# IR_array.net
KiCad netlist of a schematic drawn in Altium Designer
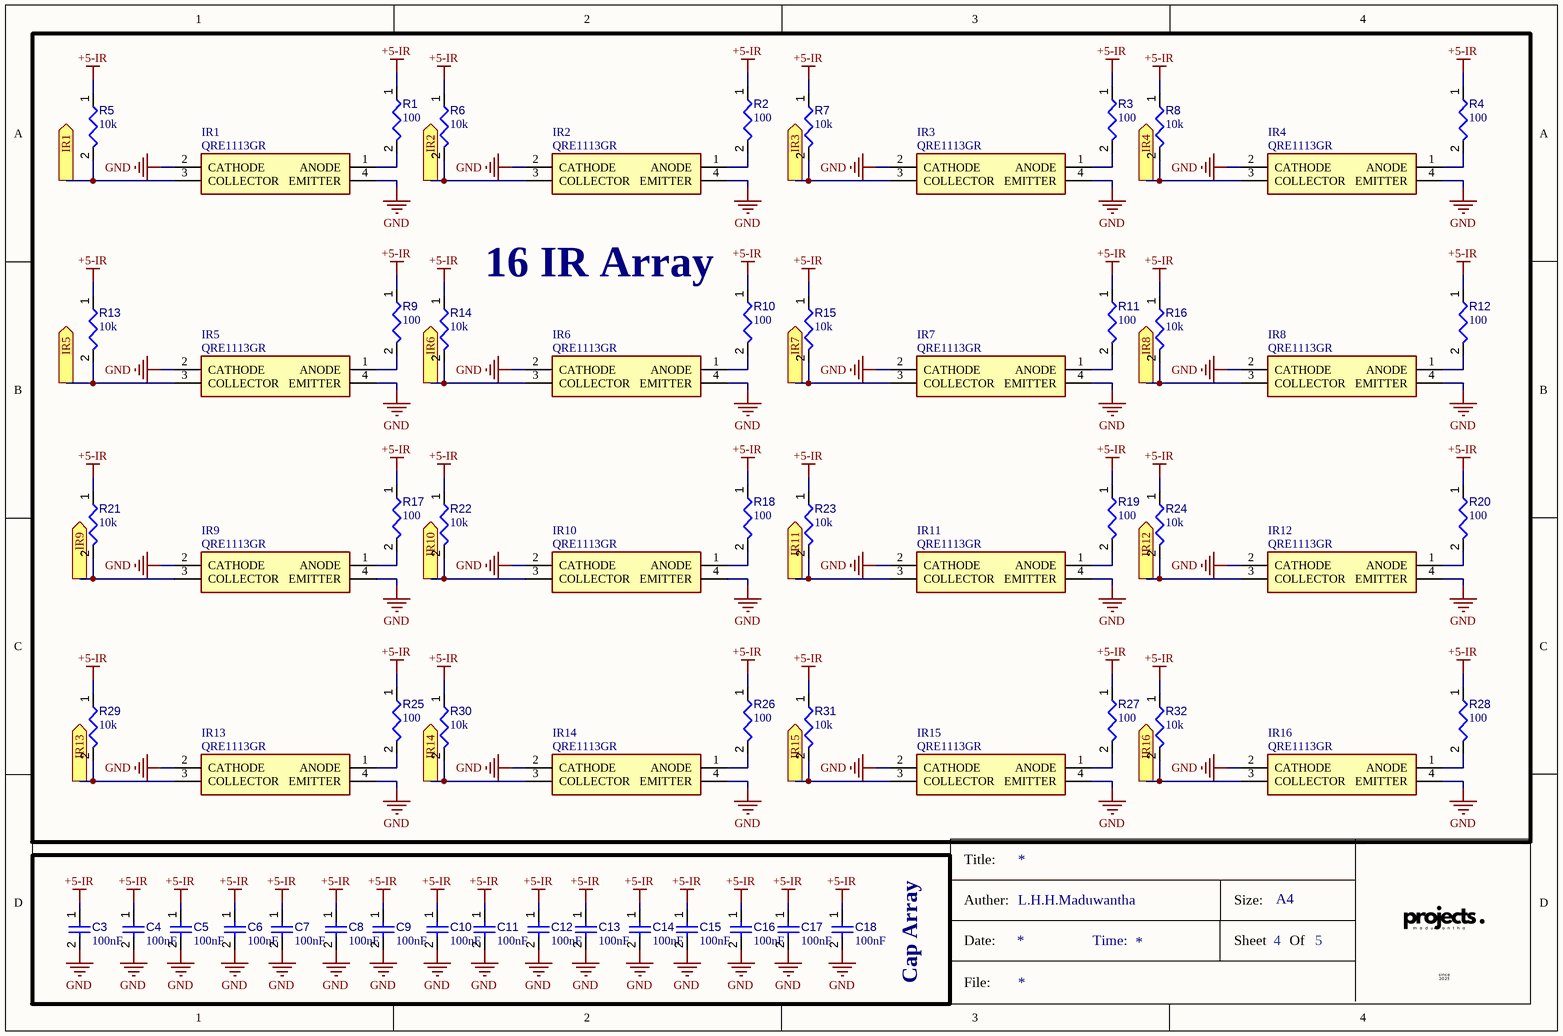
[diagram p0: IR_array.SchDoc]

(export (version "E")
  (design (tool "Eeschema 10.0.6"))
  (components
    (comp (ref "C3")
      (value "100nF")
      (footprint "CAPC2013X95X50LL10T25")
      (description "Chip Capacitor, 100 nF, +/- 10%, 50 V, 0805 (2012 Metric)")
      (fields (field (name "TOLERANCE") "10%") (field (name "Comment") "Capacitor 100 nF +/-10% 50 V 0805"))
      (libsource (lib "EDR Project") (part "CAP-NP-2"))
    )
    (comp (ref "C4")
      (value "100nF")
      (footprint "CAPC2013X95X50LL10T25")
      (description "Chip Capacitor, 100 nF, +/- 10%, 50 V, 0805 (2012 Metric)")
      (fields (field (name "TOLERANCE") "10%") (field (name "Comment") "Capacitor 100 nF +/-10% 50 V 0805"))
      (libsource (lib "EDR Project") (part "CAP-NP-2"))
    )
    (comp (ref "C5")
      (value "100nF")
      (footprint "CAPC2013X95X50LL10T25")
      (description "Chip Capacitor, 100 nF, +/- 10%, 50 V, 0805 (2012 Metric)")
      (fields (field (name "TOLERANCE") "10%") (field (name "Comment") "Capacitor 100 nF +/-10% 50 V 0805"))
      (libsource (lib "EDR Project") (part "CAP-NP-2"))
    )
    (comp (ref "C6")
      (value "100nF")
      (footprint "CAPC2013X95X50LL10T25")
      (description "Chip Capacitor, 100 nF, +/- 10%, 50 V, 0805 (2012 Metric)")
      (fields (field (name "TOLERANCE") "10%") (field (name "Comment") "Capacitor 100 nF +/-10% 50 V 0805"))
      (libsource (lib "EDR Project") (part "CAP-NP-2"))
    )
    (comp (ref "C7")
      (value "100nF")
      (footprint "CAPC2013X95X50LL10T25")
      (description "Chip Capacitor, 100 nF, +/- 10%, 50 V, 0805 (2012 Metric)")
      (fields (field (name "TOLERANCE") "10%") (field (name "Comment") "Capacitor 100 nF +/-10% 50 V 0805"))
      (libsource (lib "EDR Project") (part "CAP-NP-2"))
    )
    (comp (ref "C8")
      (value "100nF")
      (footprint "CAPC2013X95X50LL10T25")
      (description "Chip Capacitor, 100 nF, +/- 10%, 50 V, 0805 (2012 Metric)")
      (fields (field (name "TOLERANCE") "10%") (field (name "Comment") "Capacitor 100 nF +/-10% 50 V 0805"))
      (libsource (lib "EDR Project") (part "CAP-NP-2"))
    )
    (comp (ref "C9")
      (value "100nF")
      (footprint "CAPC2013X95X50LL10T25")
      (description "Chip Capacitor, 100 nF, +/- 10%, 50 V, 0805 (2012 Metric)")
      (fields (field (name "TOLERANCE") "10%") (field (name "Comment") "Capacitor 100 nF +/-10% 50 V 0805"))
      (libsource (lib "EDR Project") (part "CAP-NP-2"))
    )
    (comp (ref "C10")
      (value "100nF")
      (footprint "CAPC2013X95X50LL10T25")
      (description "Chip Capacitor, 100 nF, +/- 10%, 50 V, 0805 (2012 Metric)")
      (fields (field (name "TOLERANCE") "10%") (field (name "Comment") "Capacitor 100 nF +/-10% 50 V 0805"))
      (libsource (lib "EDR Project") (part "CAP-NP-2"))
    )
    (comp (ref "C11")
      (value "100nF")
      (footprint "CAPC2013X95X50LL10T25")
      (description "Chip Capacitor, 100 nF, +/- 10%, 50 V, 0805 (2012 Metric)")
      (fields (field (name "TOLERANCE") "10%") (field (name "Comment") "Capacitor 100 nF +/-10% 50 V 0805"))
      (libsource (lib "EDR Project") (part "CAP-NP-2"))
    )
    (comp (ref "C12")
      (value "100nF")
      (footprint "CAPC2013X95X50LL10T25")
      (description "Chip Capacitor, 100 nF, +/- 10%, 50 V, 0805 (2012 Metric)")
      (fields (field (name "TOLERANCE") "10%") (field (name "Comment") "Capacitor 100 nF +/-10% 50 V 0805"))
      (libsource (lib "EDR Project") (part "CAP-NP-2"))
    )
    (comp (ref "C13")
      (value "100nF")
      (footprint "CAPC2013X95X50LL10T25")
      (description "Chip Capacitor, 100 nF, +/- 10%, 50 V, 0805 (2012 Metric)")
      (fields (field (name "TOLERANCE") "10%") (field (name "Comment") "Capacitor 100 nF +/-10% 50 V 0805"))
      (libsource (lib "EDR Project") (part "CAP-NP-2"))
    )
    (comp (ref "C14")
      (value "100nF")
      (footprint "CAPC2013X95X50LL10T25")
      (description "Chip Capacitor, 100 nF, +/- 10%, 50 V, 0805 (2012 Metric)")
      (fields (field (name "TOLERANCE") "10%") (field (name "Comment") "Capacitor 100 nF +/-10% 50 V 0805"))
      (libsource (lib "EDR Project") (part "CAP-NP-2"))
    )
    (comp (ref "C15")
      (value "100nF")
      (footprint "CAPC2013X95X50LL10T25")
      (description "Chip Capacitor, 100 nF, +/- 10%, 50 V, 0805 (2012 Metric)")
      (fields (field (name "TOLERANCE") "10%") (field (name "Comment") "Capacitor 100 nF +/-10% 50 V 0805"))
      (libsource (lib "EDR Project") (part "CAP-NP-2"))
    )
    (comp (ref "C16")
      (value "100nF")
      (footprint "CAPC2013X95X50LL10T25")
      (description "Chip Capacitor, 100 nF, +/- 10%, 50 V, 0805 (2012 Metric)")
      (fields (field (name "TOLERANCE") "10%") (field (name "Comment") "Capacitor 100 nF +/-10% 50 V 0805"))
      (libsource (lib "EDR Project") (part "CAP-NP-2"))
    )
    (comp (ref "C17")
      (value "100nF")
      (footprint "CAPC2013X95X50LL10T25")
      (description "Chip Capacitor, 100 nF, +/- 10%, 50 V, 0805 (2012 Metric)")
      (fields (field (name "TOLERANCE") "10%") (field (name "Comment") "Capacitor 100 nF +/-10% 50 V 0805"))
      (libsource (lib "EDR Project") (part "CAP-NP-2"))
    )
    (comp (ref "C18")
      (value "100nF")
      (footprint "CAPC2013X95X50LL10T25")
      (description "Chip Capacitor, 100 nF, +/- 10%, 50 V, 0805 (2012 Metric)")
      (fields (field (name "TOLERANCE") "10%") (field (name "Comment") "Capacitor 100 nF +/-10% 50 V 0805"))
      (libsource (lib "EDR Project") (part "CAP-NP-2"))
    )
    (comp (ref "IR1")
      (value "QRE1113GR")
      (footprint "SamacSys:QRE1113GR")
      (description "Undefined or Miscellaneous")
      (fields (field (name "MOUSER PART NUMBER") "512-QRE1113GR"))
      (libsource (lib "*") (part "QRE1113GR"))
    )
    (comp (ref "IR2")
      (value "QRE1113GR")
      (footprint "SamacSys:QRE1113GR")
      (description "Undefined or Miscellaneous")
      (fields (field (name "MOUSER PART NUMBER") "512-QRE1113GR"))
      (libsource (lib "*") (part "QRE1113GR"))
    )
    (comp (ref "IR3")
      (value "QRE1113GR")
      (footprint "SamacSys:QRE1113GR")
      (description "Undefined or Miscellaneous")
      (fields (field (name "MOUSER PART NUMBER") "512-QRE1113GR"))
      (libsource (lib "*") (part "QRE1113GR"))
    )
    (comp (ref "IR4")
      (value "QRE1113GR")
      (footprint "SamacSys:QRE1113GR")
      (description "Undefined or Miscellaneous")
      (fields (field (name "MOUSER PART NUMBER") "512-QRE1113GR"))
      (libsource (lib "*") (part "QRE1113GR"))
    )
    (comp (ref "IR5")
      (value "QRE1113GR")
      (footprint "SamacSys:QRE1113GR")
      (description "Undefined or Miscellaneous")
      (fields (field (name "MOUSER PART NUMBER") "512-QRE1113GR"))
      (libsource (lib "*") (part "QRE1113GR"))
    )
    (comp (ref "IR6")
      (value "QRE1113GR")
      (footprint "SamacSys:QRE1113GR")
      (description "Undefined or Miscellaneous")
      (fields (field (name "MOUSER PART NUMBER") "512-QRE1113GR"))
      (libsource (lib "*") (part "QRE1113GR"))
    )
    (comp (ref "IR7")
      (value "QRE1113GR")
      (footprint "SamacSys:QRE1113GR")
      (description "Undefined or Miscellaneous")
      (fields (field (name "MOUSER PART NUMBER") "512-QRE1113GR"))
      (libsource (lib "*") (part "QRE1113GR"))
    )
    (comp (ref "IR8")
      (value "QRE1113GR")
      (footprint "SamacSys:QRE1113GR")
      (description "Undefined or Miscellaneous")
      (fields (field (name "MOUSER PART NUMBER") "512-QRE1113GR"))
      (libsource (lib "*") (part "QRE1113GR"))
    )
    (comp (ref "IR9")
      (value "QRE1113GR")
      (footprint "SamacSys:QRE1113GR")
      (description "Undefined or Miscellaneous")
      (fields (field (name "MOUSER PART NUMBER") "512-QRE1113GR"))
      (libsource (lib "*") (part "QRE1113GR"))
    )
    (comp (ref "IR10")
      (value "QRE1113GR")
      (footprint "SamacSys:QRE1113GR")
      (description "Undefined or Miscellaneous")
      (fields (field (name "MOUSER PART NUMBER") "512-QRE1113GR"))
      (libsource (lib "*") (part "QRE1113GR"))
    )
    (comp (ref "IR11")
      (value "QRE1113GR")
      (footprint "SamacSys:QRE1113GR")
      (description "Undefined or Miscellaneous")
      (fields (field (name "MOUSER PART NUMBER") "512-QRE1113GR"))
      (libsource (lib "*") (part "QRE1113GR"))
    )
    (comp (ref "IR12")
      (value "QRE1113GR")
      (footprint "SamacSys:QRE1113GR")
      (description "Undefined or Miscellaneous")
      (fields (field (name "MOUSER PART NUMBER") "512-QRE1113GR"))
      (libsource (lib "*") (part "QRE1113GR"))
    )
    (comp (ref "IR13")
      (value "QRE1113GR")
      (footprint "SamacSys:QRE1113GR")
      (description "Undefined or Miscellaneous")
      (fields (field (name "MOUSER PART NUMBER") "512-QRE1113GR"))
      (libsource (lib "*") (part "QRE1113GR"))
    )
    (comp (ref "IR14")
      (value "QRE1113GR")
      (footprint "SamacSys:QRE1113GR")
      (description "Undefined or Miscellaneous")
      (fields (field (name "MOUSER PART NUMBER") "512-QRE1113GR"))
      (libsource (lib "*") (part "QRE1113GR"))
    )
    (comp (ref "IR15")
      (value "QRE1113GR")
      (footprint "SamacSys:QRE1113GR")
      (description "Undefined or Miscellaneous")
      (fields (field (name "MOUSER PART NUMBER") "512-QRE1113GR"))
      (libsource (lib "*") (part "QRE1113GR"))
    )
    (comp (ref "IR16")
      (value "QRE1113GR")
      (footprint "SamacSys:QRE1113GR")
      (description "Undefined or Miscellaneous")
      (fields (field (name "MOUSER PART NUMBER") "512-QRE1113GR"))
      (libsource (lib "*") (part "QRE1113GR"))
    )
    (comp (ref "R1")
      (value "100")
      (footprint "RESC2013X70X40ML20T20")
      (description "Chip Resistor, 100 KOhm, +/- 1%, 0.125 W, -55 to 155 degC, 0805 (2012 Metric)")
      (fields (field (name "POWER") "125mW") (field (name "TOLERANCE") "1%"))
      (libsource (lib "EDR Project") (part "RES-2"))
    )
    (comp (ref "R2")
      (value "100")
      (footprint "RESC2013X70X40ML20T20")
      (description "Chip Resistor, 100 KOhm, +/- 1%, 0.125 W, -55 to 155 degC, 0805 (2012 Metric)")
      (fields (field (name "POWER") "125mW") (field (name "TOLERANCE") "1%"))
      (libsource (lib "EDR Project") (part "RES-2"))
    )
    (comp (ref "R3")
      (value "100")
      (footprint "RESC2013X70X40ML20T20")
      (description "Chip Resistor, 100 KOhm, +/- 1%, 0.125 W, -55 to 155 degC, 0805 (2012 Metric)")
      (fields (field (name "POWER") "125mW") (field (name "TOLERANCE") "1%"))
      (libsource (lib "EDR Project") (part "RES-2"))
    )
    (comp (ref "R4")
      (value "100")
      (footprint "RESC2013X70X40ML20T20")
      (description "Chip Resistor, 100 KOhm, +/- 1%, 0.125 W, -55 to 155 degC, 0805 (2012 Metric)")
      (fields (field (name "POWER") "125mW") (field (name "TOLERANCE") "1%"))
      (libsource (lib "EDR Project") (part "RES-2"))
    )
    (comp (ref "R5")
      (value "10k")
      (footprint "RESC2013X50X35ML15T15")
      (description "Chip Resistor, 10 KOhm, +/- 1%, 125 mW, -55 to 155 degC, 0805 (2012 Metric)")
      (fields (field (name "TOLERANCE") "1%") (field (name "POWER") "125mW"))
      (libsource (lib "EDR Project") (part "RES-2"))
    )
    (comp (ref "R6")
      (value "10k")
      (footprint "RESC2013X50X35ML15T15")
      (description "Chip Resistor, 10 KOhm, +/- 1%, 125 mW, -55 to 155 degC, 0805 (2012 Metric)")
      (fields (field (name "TOLERANCE") "1%") (field (name "POWER") "125mW"))
      (libsource (lib "EDR Project") (part "RES-2"))
    )
    (comp (ref "R7")
      (value "10k")
      (footprint "RESC2013X50X35ML15T15")
      (description "Chip Resistor, 10 KOhm, +/- 1%, 125 mW, -55 to 155 degC, 0805 (2012 Metric)")
      (fields (field (name "TOLERANCE") "1%") (field (name "POWER") "125mW"))
      (libsource (lib "EDR Project") (part "RES-2"))
    )
    (comp (ref "R8")
      (value "10k")
      (footprint "RESC2013X50X35ML15T15")
      (description "Chip Resistor, 10 KOhm, +/- 1%, 125 mW, -55 to 155 degC, 0805 (2012 Metric)")
      (fields (field (name "TOLERANCE") "1%") (field (name "POWER") "125mW"))
      (libsource (lib "EDR Project") (part "RES-2"))
    )
    (comp (ref "R9")
      (value "100")
      (footprint "RESC2013X70X40ML20T20")
      (description "Chip Resistor, 100 KOhm, +/- 1%, 0.125 W, -55 to 155 degC, 0805 (2012 Metric)")
      (fields (field (name "POWER") "125mW") (field (name "TOLERANCE") "1%"))
      (libsource (lib "EDR Project") (part "RES-2"))
    )
    (comp (ref "R10")
      (value "100")
      (footprint "RESC2013X70X40ML20T20")
      (description "Chip Resistor, 100 KOhm, +/- 1%, 0.125 W, -55 to 155 degC, 0805 (2012 Metric)")
      (fields (field (name "POWER") "125mW") (field (name "TOLERANCE") "1%"))
      (libsource (lib "EDR Project") (part "RES-2"))
    )
    (comp (ref "R11")
      (value "100")
      (footprint "RESC2013X70X40ML20T20")
      (description "Chip Resistor, 100 KOhm, +/- 1%, 0.125 W, -55 to 155 degC, 0805 (2012 Metric)")
      (fields (field (name "POWER") "125mW") (field (name "TOLERANCE") "1%"))
      (libsource (lib "EDR Project") (part "RES-2"))
    )
    (comp (ref "R12")
      (value "100")
      (footprint "RESC2013X70X40ML20T20")
      (description "Chip Resistor, 100 KOhm, +/- 1%, 0.125 W, -55 to 155 degC, 0805 (2012 Metric)")
      (fields (field (name "POWER") "125mW") (field (name "TOLERANCE") "1%"))
      (libsource (lib "EDR Project") (part "RES-2"))
    )
    (comp (ref "R13")
      (value "10k")
      (footprint "RESC2013X50X35ML15T15")
      (description "Chip Resistor, 10 KOhm, +/- 1%, 125 mW, -55 to 155 degC, 0805 (2012 Metric)")
      (fields (field (name "TOLERANCE") "1%") (field (name "POWER") "125mW"))
      (libsource (lib "EDR Project") (part "RES-2"))
    )
    (comp (ref "R14")
      (value "10k")
      (footprint "RESC2013X50X35ML15T15")
      (description "Chip Resistor, 10 KOhm, +/- 1%, 125 mW, -55 to 155 degC, 0805 (2012 Metric)")
      (fields (field (name "TOLERANCE") "1%") (field (name "POWER") "125mW"))
      (libsource (lib "EDR Project") (part "RES-2"))
    )
    (comp (ref "R15")
      (value "10k")
      (footprint "RESC2013X50X35ML15T15")
      (description "Chip Resistor, 10 KOhm, +/- 1%, 125 mW, -55 to 155 degC, 0805 (2012 Metric)")
      (fields (field (name "TOLERANCE") "1%") (field (name "POWER") "125mW"))
      (libsource (lib "EDR Project") (part "RES-2"))
    )
    (comp (ref "R16")
      (value "10k")
      (footprint "RESC2013X50X35ML15T15")
      (description "Chip Resistor, 10 KOhm, +/- 1%, 125 mW, -55 to 155 degC, 0805 (2012 Metric)")
      (fields (field (name "TOLERANCE") "1%") (field (name "POWER") "125mW"))
      (libsource (lib "EDR Project") (part "RES-2"))
    )
    (comp (ref "R17")
      (value "100")
      (footprint "RESC2013X70X40ML20T20")
      (description "Chip Resistor, 100 KOhm, +/- 1%, 0.125 W, -55 to 155 degC, 0805 (2012 Metric)")
      (fields (field (name "POWER") "125mW") (field (name "TOLERANCE") "1%"))
      (libsource (lib "EDR Project") (part "RES-2"))
    )
    (comp (ref "R18")
      (value "100")
      (footprint "RESC2013X70X40ML20T20")
      (description "Chip Resistor, 100 KOhm, +/- 1%, 0.125 W, -55 to 155 degC, 0805 (2012 Metric)")
      (fields (field (name "POWER") "125mW") (field (name "TOLERANCE") "1%"))
      (libsource (lib "EDR Project") (part "RES-2"))
    )
    (comp (ref "R19")
      (value "100")
      (footprint "RESC2013X70X40ML20T20")
      (description "Chip Resistor, 100 KOhm, +/- 1%, 0.125 W, -55 to 155 degC, 0805 (2012 Metric)")
      (fields (field (name "POWER") "125mW") (field (name "TOLERANCE") "1%"))
      (libsource (lib "EDR Project") (part "RES-2"))
    )
    (comp (ref "R20")
      (value "100")
      (footprint "RESC2013X70X40ML20T20")
      (description "Chip Resistor, 100 KOhm, +/- 1%, 0.125 W, -55 to 155 degC, 0805 (2012 Metric)")
      (fields (field (name "POWER") "125mW") (field (name "TOLERANCE") "1%"))
      (libsource (lib "EDR Project") (part "RES-2"))
    )
    (comp (ref "R21")
      (value "10k")
      (footprint "RESC2013X50X35ML15T15")
      (description "Chip Resistor, 10 KOhm, +/- 1%, 125 mW, -55 to 155 degC, 0805 (2012 Metric)")
      (fields (field (name "TOLERANCE") "1%") (field (name "POWER") "125mW"))
      (libsource (lib "EDR Project") (part "RES-2"))
    )
    (comp (ref "R22")
      (value "10k")
      (footprint "RESC2013X50X35ML15T15")
      (description "Chip Resistor, 10 KOhm, +/- 1%, 125 mW, -55 to 155 degC, 0805 (2012 Metric)")
      (fields (field (name "TOLERANCE") "1%") (field (name "POWER") "125mW"))
      (libsource (lib "EDR Project") (part "RES-2"))
    )
    (comp (ref "R23")
      (value "10k")
      (footprint "RESC2013X50X35ML15T15")
      (description "Chip Resistor, 10 KOhm, +/- 1%, 125 mW, -55 to 155 degC, 0805 (2012 Metric)")
      (fields (field (name "TOLERANCE") "1%") (field (name "POWER") "125mW"))
      (libsource (lib "EDR Project") (part "RES-2"))
    )
    (comp (ref "R24")
      (value "10k")
      (footprint "RESC2013X50X35ML15T15")
      (description "Chip Resistor, 10 KOhm, +/- 1%, 125 mW, -55 to 155 degC, 0805 (2012 Metric)")
      (fields (field (name "TOLERANCE") "1%") (field (name "POWER") "125mW"))
      (libsource (lib "EDR Project") (part "RES-2"))
    )
    (comp (ref "R25")
      (value "100")
      (footprint "RESC2013X70X40ML20T20")
      (description "Chip Resistor, 100 KOhm, +/- 1%, 0.125 W, -55 to 155 degC, 0805 (2012 Metric)")
      (fields (field (name "POWER") "125mW") (field (name "TOLERANCE") "1%"))
      (libsource (lib "EDR Project") (part "RES-2"))
    )
    (comp (ref "R26")
      (value "100")
      (footprint "RESC2013X70X40ML20T20")
      (description "Chip Resistor, 100 KOhm, +/- 1%, 0.125 W, -55 to 155 degC, 0805 (2012 Metric)")
      (fields (field (name "POWER") "125mW") (field (name "TOLERANCE") "1%"))
      (libsource (lib "EDR Project") (part "RES-2"))
    )
    (comp (ref "R27")
      (value "100")
      (footprint "RESC2013X70X40ML20T20")
      (description "Chip Resistor, 100 KOhm, +/- 1%, 0.125 W, -55 to 155 degC, 0805 (2012 Metric)")
      (fields (field (name "POWER") "125mW") (field (name "TOLERANCE") "1%"))
      (libsource (lib "EDR Project") (part "RES-2"))
    )
    (comp (ref "R28")
      (value "100")
      (footprint "RESC2013X70X40ML20T20")
      (description "Chip Resistor, 100 KOhm, +/- 1%, 0.125 W, -55 to 155 degC, 0805 (2012 Metric)")
      (fields (field (name "POWER") "125mW") (field (name "TOLERANCE") "1%"))
      (libsource (lib "EDR Project") (part "RES-2"))
    )
    (comp (ref "R29")
      (value "10k")
      (footprint "RESC2013X50X35ML15T15")
      (description "Chip Resistor, 10 KOhm, +/- 1%, 125 mW, -55 to 155 degC, 0805 (2012 Metric)")
      (fields (field (name "TOLERANCE") "1%") (field (name "POWER") "125mW"))
      (libsource (lib "EDR Project") (part "RES-2"))
    )
    (comp (ref "R30")
      (value "10k")
      (footprint "RESC2013X50X35ML15T15")
      (description "Chip Resistor, 10 KOhm, +/- 1%, 125 mW, -55 to 155 degC, 0805 (2012 Metric)")
      (fields (field (name "TOLERANCE") "1%") (field (name "POWER") "125mW"))
      (libsource (lib "EDR Project") (part "RES-2"))
    )
    (comp (ref "R31")
      (value "10k")
      (footprint "RESC2013X50X35ML15T15")
      (description "Chip Resistor, 10 KOhm, +/- 1%, 125 mW, -55 to 155 degC, 0805 (2012 Metric)")
      (fields (field (name "TOLERANCE") "1%") (field (name "POWER") "125mW"))
      (libsource (lib "EDR Project") (part "RES-2"))
    )
    (comp (ref "R32")
      (value "10k")
      (footprint "RESC2013X50X35ML15T15")
      (description "Chip Resistor, 10 KOhm, +/- 1%, 125 mW, -55 to 155 degC, 0805 (2012 Metric)")
      (fields (field (name "TOLERANCE") "1%") (field (name "POWER") "125mW"))
      (libsource (lib "EDR Project") (part "RES-2"))
    )
  )
  (nets
    (net (code "1") (name "+5-IR") (class "Default")
      (node (ref "C10") (pin "1") (pinfunction "1_1") (pintype "passive"))
      (node (ref "C11") (pin "1") (pinfunction "1_1") (pintype "passive"))
      (node (ref "C12") (pin "1") (pinfunction "1_1") (pintype "passive"))
      (node (ref "C13") (pin "1") (pinfunction "1_1") (pintype "passive"))
      (node (ref "C14") (pin "1") (pinfunction "1_1") (pintype "passive"))
      (node (ref "C15") (pin "1") (pinfunction "1_1") (pintype "passive"))
      (node (ref "C16") (pin "1") (pinfunction "1_1") (pintype "passive"))
      (node (ref "C17") (pin "1") (pinfunction "1_1") (pintype "passive"))
      (node (ref "C18") (pin "1") (pinfunction "1_1") (pintype "passive"))
      (node (ref "C3") (pin "1") (pinfunction "1_1") (pintype "passive"))
      (node (ref "C4") (pin "1") (pinfunction "1_1") (pintype "passive"))
      (node (ref "C5") (pin "1") (pinfunction "1_1") (pintype "passive"))
      (node (ref "C6") (pin "1") (pinfunction "1_1") (pintype "passive"))
      (node (ref "C7") (pin "1") (pinfunction "1_1") (pintype "passive"))
      (node (ref "C8") (pin "1") (pinfunction "1_1") (pintype "passive"))
      (node (ref "C9") (pin "1") (pinfunction "1_1") (pintype "passive"))
      (node (ref "R1") (pin "1") (pinfunction "1_1") (pintype "passive"))
      (node (ref "R10") (pin "1") (pinfunction "1_1") (pintype "passive"))
      (node (ref "R11") (pin "1") (pinfunction "1_1") (pintype "passive"))
      (node (ref "R12") (pin "1") (pinfunction "1_1") (pintype "passive"))
      (node (ref "R13") (pin "1") (pinfunction "1_1") (pintype "passive"))
      (node (ref "R14") (pin "1") (pinfunction "1_1") (pintype "passive"))
      (node (ref "R15") (pin "1") (pinfunction "1_1") (pintype "passive"))
      (node (ref "R16") (pin "1") (pinfunction "1_1") (pintype "passive"))
      (node (ref "R17") (pin "1") (pinfunction "1_1") (pintype "passive"))
      (node (ref "R18") (pin "1") (pinfunction "1_1") (pintype "passive"))
      (node (ref "R19") (pin "1") (pinfunction "1_1") (pintype "passive"))
      (node (ref "R2") (pin "1") (pinfunction "1_1") (pintype "passive"))
      (node (ref "R20") (pin "1") (pinfunction "1_1") (pintype "passive"))
      (node (ref "R21") (pin "1") (pinfunction "1_1") (pintype "passive"))
      (node (ref "R22") (pin "1") (pinfunction "1_1") (pintype "passive"))
      (node (ref "R23") (pin "1") (pinfunction "1_1") (pintype "passive"))
      (node (ref "R24") (pin "1") (pinfunction "1_1") (pintype "passive"))
      (node (ref "R25") (pin "1") (pinfunction "1_1") (pintype "passive"))
      (node (ref "R26") (pin "1") (pinfunction "1_1") (pintype "passive"))
      (node (ref "R27") (pin "1") (pinfunction "1_1") (pintype "passive"))
      (node (ref "R28") (pin "1") (pinfunction "1_1") (pintype "passive"))
      (node (ref "R29") (pin "1") (pinfunction "1_1") (pintype "passive"))
      (node (ref "R3") (pin "1") (pinfunction "1_1") (pintype "passive"))
      (node (ref "R30") (pin "1") (pinfunction "1_1") (pintype "passive"))
      (node (ref "R31") (pin "1") (pinfunction "1_1") (pintype "passive"))
      (node (ref "R32") (pin "1") (pinfunction "1_1") (pintype "passive"))
      (node (ref "R4") (pin "1") (pinfunction "1_1") (pintype "passive"))
      (node (ref "R5") (pin "1") (pinfunction "1_1") (pintype "passive"))
      (node (ref "R6") (pin "1") (pinfunction "1_1") (pintype "passive"))
      (node (ref "R7") (pin "1") (pinfunction "1_1") (pintype "passive"))
      (node (ref "R8") (pin "1") (pinfunction "1_1") (pintype "passive"))
      (node (ref "R9") (pin "1") (pinfunction "1_1") (pintype "passive"))
    )
    (net (code "2") (name "/IR1") (class "Default")
      (node (ref "IR1") (pin "3") (pinfunction "COLLECTOR_3") (pintype "passive"))
      (node (ref "R5") (pin "2") (pinfunction "2_2") (pintype "passive"))
    )
    (net (code "3") (name "/IR2") (class "Default")
      (node (ref "IR2") (pin "3") (pinfunction "COLLECTOR_3") (pintype "passive"))
      (node (ref "R6") (pin "2") (pinfunction "2_2") (pintype "passive"))
    )
    (net (code "4") (name "/IR3") (class "Default")
      (node (ref "IR3") (pin "3") (pinfunction "COLLECTOR_3") (pintype "passive"))
      (node (ref "R7") (pin "2") (pinfunction "2_2") (pintype "passive"))
    )
    (net (code "5") (name "/IR4") (class "Default")
      (node (ref "IR4") (pin "3") (pinfunction "COLLECTOR_3") (pintype "passive"))
      (node (ref "R8") (pin "2") (pinfunction "2_2") (pintype "passive"))
    )
    (net (code "6") (name "/IR5") (class "Default")
      (node (ref "IR5") (pin "3") (pinfunction "COLLECTOR_3") (pintype "passive"))
      (node (ref "R13") (pin "2") (pinfunction "2_2") (pintype "passive"))
    )
    (net (code "7") (name "/IR6") (class "Default")
      (node (ref "IR6") (pin "3") (pinfunction "COLLECTOR_3") (pintype "passive"))
      (node (ref "R14") (pin "2") (pinfunction "2_2") (pintype "passive"))
    )
    (net (code "8") (name "/IR7") (class "Default")
      (node (ref "IR7") (pin "3") (pinfunction "COLLECTOR_3") (pintype "passive"))
      (node (ref "R15") (pin "2") (pinfunction "2_2") (pintype "passive"))
    )
    (net (code "9") (name "/IR8") (class "Default")
      (node (ref "IR8") (pin "3") (pinfunction "COLLECTOR_3") (pintype "passive"))
      (node (ref "R16") (pin "2") (pinfunction "2_2") (pintype "passive"))
    )
    (net (code "10") (name "/IR9") (class "Default")
      (node (ref "IR9") (pin "3") (pinfunction "COLLECTOR_3") (pintype "passive"))
      (node (ref "R21") (pin "2") (pinfunction "2_2") (pintype "passive"))
    )
    (net (code "11") (name "/IR10") (class "Default")
      (node (ref "IR10") (pin "3") (pinfunction "COLLECTOR_3") (pintype "passive"))
      (node (ref "R22") (pin "2") (pinfunction "2_2") (pintype "passive"))
    )
    (net (code "12") (name "/IR11") (class "Default")
      (node (ref "IR11") (pin "3") (pinfunction "COLLECTOR_3") (pintype "passive"))
      (node (ref "R23") (pin "2") (pinfunction "2_2") (pintype "passive"))
    )
    (net (code "13") (name "/IR12") (class "Default")
      (node (ref "IR12") (pin "3") (pinfunction "COLLECTOR_3") (pintype "passive"))
      (node (ref "R24") (pin "2") (pinfunction "2_2") (pintype "passive"))
    )
    (net (code "14") (name "/IR13") (class "Default")
      (node (ref "IR13") (pin "3") (pinfunction "COLLECTOR_3") (pintype "passive"))
      (node (ref "R29") (pin "2") (pinfunction "2_2") (pintype "passive"))
    )
    (net (code "15") (name "/IR14") (class "Default")
      (node (ref "IR14") (pin "3") (pinfunction "COLLECTOR_3") (pintype "passive"))
      (node (ref "R30") (pin "2") (pinfunction "2_2") (pintype "passive"))
    )
    (net (code "16") (name "/IR15") (class "Default")
      (node (ref "IR15") (pin "3") (pinfunction "COLLECTOR_3") (pintype "passive"))
      (node (ref "R31") (pin "2") (pinfunction "2_2") (pintype "passive"))
    )
    (net (code "17") (name "/IR16") (class "Default")
      (node (ref "IR16") (pin "3") (pinfunction "COLLECTOR_3") (pintype "passive"))
      (node (ref "R32") (pin "2") (pinfunction "2_2") (pintype "passive"))
    )
    (net (code "18") (name "GND") (class "Default")
      (node (ref "C10") (pin "2") (pinfunction "2_2") (pintype "passive"))
      (node (ref "C11") (pin "2") (pinfunction "2_2") (pintype "passive"))
      (node (ref "C12") (pin "2") (pinfunction "2_2") (pintype "passive"))
      (node (ref "C13") (pin "2") (pinfunction "2_2") (pintype "passive"))
      (node (ref "C14") (pin "2") (pinfunction "2_2") (pintype "passive"))
      (node (ref "C15") (pin "2") (pinfunction "2_2") (pintype "passive"))
      (node (ref "C16") (pin "2") (pinfunction "2_2") (pintype "passive"))
      (node (ref "C17") (pin "2") (pinfunction "2_2") (pintype "passive"))
      (node (ref "C18") (pin "2") (pinfunction "2_2") (pintype "passive"))
      (node (ref "C3") (pin "2") (pinfunction "2_2") (pintype "passive"))
      (node (ref "C4") (pin "2") (pinfunction "2_2") (pintype "passive"))
      (node (ref "C5") (pin "2") (pinfunction "2_2") (pintype "passive"))
      (node (ref "C6") (pin "2") (pinfunction "2_2") (pintype "passive"))
      (node (ref "C7") (pin "2") (pinfunction "2_2") (pintype "passive"))
      (node (ref "C8") (pin "2") (pinfunction "2_2") (pintype "passive"))
      (node (ref "C9") (pin "2") (pinfunction "2_2") (pintype "passive"))
      (node (ref "IR1") (pin "2") (pinfunction "CATHODE_2") (pintype "passive"))
      (node (ref "IR1") (pin "4") (pinfunction "EMITTER_4") (pintype "passive"))
      (node (ref "IR10") (pin "2") (pinfunction "CATHODE_2") (pintype "passive"))
      (node (ref "IR10") (pin "4") (pinfunction "EMITTER_4") (pintype "passive"))
      (node (ref "IR11") (pin "2") (pinfunction "CATHODE_2") (pintype "passive"))
      (node (ref "IR11") (pin "4") (pinfunction "EMITTER_4") (pintype "passive"))
      (node (ref "IR12") (pin "2") (pinfunction "CATHODE_2") (pintype "passive"))
      (node (ref "IR12") (pin "4") (pinfunction "EMITTER_4") (pintype "passive"))
      (node (ref "IR13") (pin "2") (pinfunction "CATHODE_2") (pintype "passive"))
      (node (ref "IR13") (pin "4") (pinfunction "EMITTER_4") (pintype "passive"))
      (node (ref "IR14") (pin "2") (pinfunction "CATHODE_2") (pintype "passive"))
      (node (ref "IR14") (pin "4") (pinfunction "EMITTER_4") (pintype "passive"))
      (node (ref "IR15") (pin "2") (pinfunction "CATHODE_2") (pintype "passive"))
      (node (ref "IR15") (pin "4") (pinfunction "EMITTER_4") (pintype "passive"))
      (node (ref "IR16") (pin "2") (pinfunction "CATHODE_2") (pintype "passive"))
      (node (ref "IR16") (pin "4") (pinfunction "EMITTER_4") (pintype "passive"))
      (node (ref "IR2") (pin "2") (pinfunction "CATHODE_2") (pintype "passive"))
      (node (ref "IR2") (pin "4") (pinfunction "EMITTER_4") (pintype "passive"))
      (node (ref "IR3") (pin "2") (pinfunction "CATHODE_2") (pintype "passive"))
      (node (ref "IR3") (pin "4") (pinfunction "EMITTER_4") (pintype "passive"))
      (node (ref "IR4") (pin "2") (pinfunction "CATHODE_2") (pintype "passive"))
      (node (ref "IR4") (pin "4") (pinfunction "EMITTER_4") (pintype "passive"))
      (node (ref "IR5") (pin "2") (pinfunction "CATHODE_2") (pintype "passive"))
      (node (ref "IR5") (pin "4") (pinfunction "EMITTER_4") (pintype "passive"))
      (node (ref "IR6") (pin "2") (pinfunction "CATHODE_2") (pintype "passive"))
      (node (ref "IR6") (pin "4") (pinfunction "EMITTER_4") (pintype "passive"))
      (node (ref "IR7") (pin "2") (pinfunction "CATHODE_2") (pintype "passive"))
      (node (ref "IR7") (pin "4") (pinfunction "EMITTER_4") (pintype "passive"))
      (node (ref "IR8") (pin "2") (pinfunction "CATHODE_2") (pintype "passive"))
      (node (ref "IR8") (pin "4") (pinfunction "EMITTER_4") (pintype "passive"))
      (node (ref "IR9") (pin "2") (pinfunction "CATHODE_2") (pintype "passive"))
      (node (ref "IR9") (pin "4") (pinfunction "EMITTER_4") (pintype "passive"))
    )
    (net (code "19") (name "Net-(IR1-ANODE)") (class "Default")
      (node (ref "IR1") (pin "1") (pinfunction "ANODE_1") (pintype "passive"))
      (node (ref "R1") (pin "2") (pinfunction "2_2") (pintype "passive"))
    )
    (net (code "20") (name "Net-(IR2-ANODE)") (class "Default")
      (node (ref "IR2") (pin "1") (pinfunction "ANODE_1") (pintype "passive"))
      (node (ref "R2") (pin "2") (pinfunction "2_2") (pintype "passive"))
    )
    (net (code "21") (name "Net-(IR3-ANODE)") (class "Default")
      (node (ref "IR3") (pin "1") (pinfunction "ANODE_1") (pintype "passive"))
      (node (ref "R3") (pin "2") (pinfunction "2_2") (pintype "passive"))
    )
    (net (code "22") (name "Net-(IR4-ANODE)") (class "Default")
      (node (ref "IR4") (pin "1") (pinfunction "ANODE_1") (pintype "passive"))
      (node (ref "R4") (pin "2") (pinfunction "2_2") (pintype "passive"))
    )
    (net (code "23") (name "Net-(IR5-ANODE)") (class "Default")
      (node (ref "IR5") (pin "1") (pinfunction "ANODE_1") (pintype "passive"))
      (node (ref "R9") (pin "2") (pinfunction "2_2") (pintype "passive"))
    )
    (net (code "24") (name "Net-(IR6-ANODE)") (class "Default")
      (node (ref "IR6") (pin "1") (pinfunction "ANODE_1") (pintype "passive"))
      (node (ref "R10") (pin "2") (pinfunction "2_2") (pintype "passive"))
    )
    (net (code "25") (name "Net-(IR7-ANODE)") (class "Default")
      (node (ref "IR7") (pin "1") (pinfunction "ANODE_1") (pintype "passive"))
      (node (ref "R11") (pin "2") (pinfunction "2_2") (pintype "passive"))
    )
    (net (code "26") (name "Net-(IR8-ANODE)") (class "Default")
      (node (ref "IR8") (pin "1") (pinfunction "ANODE_1") (pintype "passive"))
      (node (ref "R12") (pin "2") (pinfunction "2_2") (pintype "passive"))
    )
    (net (code "27") (name "Net-(IR9-ANODE)") (class "Default")
      (node (ref "IR9") (pin "1") (pinfunction "ANODE_1") (pintype "passive"))
      (node (ref "R17") (pin "2") (pinfunction "2_2") (pintype "passive"))
    )
    (net (code "28") (name "Net-(IR10-ANODE)") (class "Default")
      (node (ref "IR10") (pin "1") (pinfunction "ANODE_1") (pintype "passive"))
      (node (ref "R18") (pin "2") (pinfunction "2_2") (pintype "passive"))
    )
    (net (code "29") (name "Net-(IR11-ANODE)") (class "Default")
      (node (ref "IR11") (pin "1") (pinfunction "ANODE_1") (pintype "passive"))
      (node (ref "R19") (pin "2") (pinfunction "2_2") (pintype "passive"))
    )
    (net (code "30") (name "Net-(IR12-ANODE)") (class "Default")
      (node (ref "IR12") (pin "1") (pinfunction "ANODE_1") (pintype "passive"))
      (node (ref "R20") (pin "2") (pinfunction "2_2") (pintype "passive"))
    )
    (net (code "31") (name "Net-(IR13-ANODE)") (class "Default")
      (node (ref "IR13") (pin "1") (pinfunction "ANODE_1") (pintype "passive"))
      (node (ref "R25") (pin "2") (pinfunction "2_2") (pintype "passive"))
    )
    (net (code "32") (name "Net-(IR14-ANODE)") (class "Default")
      (node (ref "IR14") (pin "1") (pinfunction "ANODE_1") (pintype "passive"))
      (node (ref "R26") (pin "2") (pinfunction "2_2") (pintype "passive"))
    )
    (net (code "33") (name "Net-(IR15-ANODE)") (class "Default")
      (node (ref "IR15") (pin "1") (pinfunction "ANODE_1") (pintype "passive"))
      (node (ref "R27") (pin "2") (pinfunction "2_2") (pintype "passive"))
    )
    (net (code "34") (name "Net-(IR16-ANODE)") (class "Default")
      (node (ref "IR16") (pin "1") (pinfunction "ANODE_1") (pintype "passive"))
      (node (ref "R28") (pin "2") (pinfunction "2_2") (pintype "passive"))
    )
  )
)
